# LV_power.net
KiCad netlist of a schematic drawn in Altium Designer
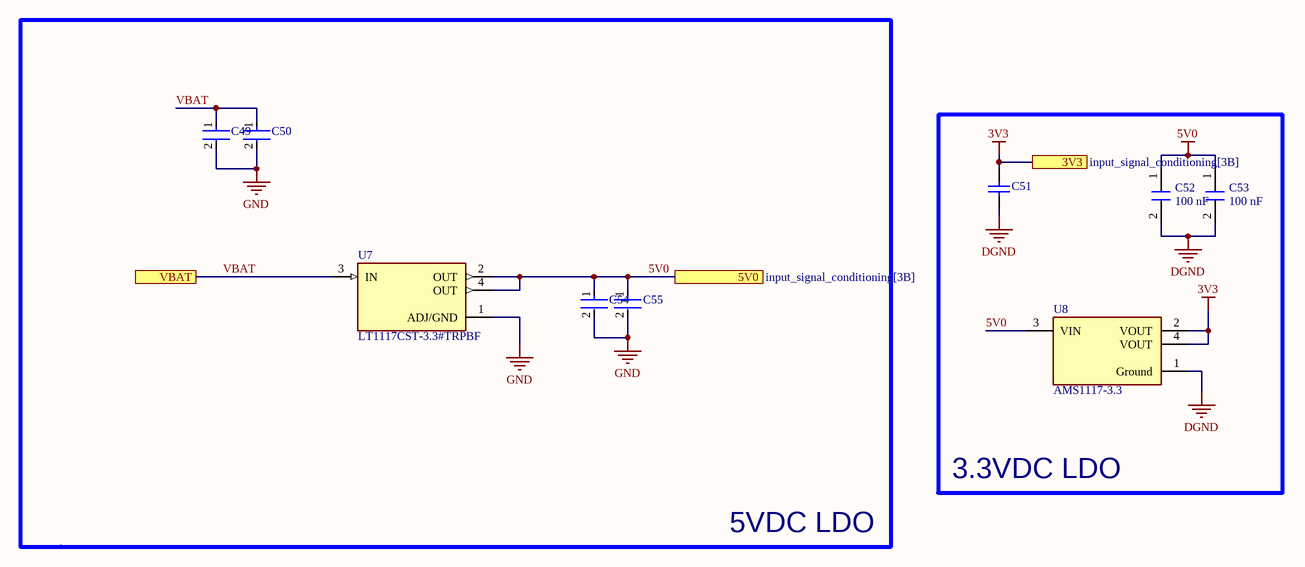
[diagram p0: LV_power.SchDoc]

(export (version "E")
  (design (tool "Eeschema 10.0.6"))
  (components
    (comp (ref "C49")
      (value "CC0805MKX5R8BB226")
      (footprint "FP-CC0805-0_2-1_45-IPC_C")
      (description "CAP CER 22UF 25V X5R 0805")
      (fields (field (name "TOLERANCE") "20%"))
      (libsource (lib "Altium Content Vault") (part "11868f565c42a9108669ba33697ecf6"))
    )
    (comp (ref "C50")
      (value "CC0805MKX5R8BB226")
      (footprint "FP-CC0805-0_2-1_45-IPC_C")
      (description "CAP CER 22UF 25V X5R 0805")
      (fields (field (name "TOLERANCE") "20%"))
      (libsource (lib "Altium Content Vault") (part "11868f565c42a9108669ba33697ecf6"))
    )
    (comp (ref "C51")
      (value "0805ZG106ZAT2A")
      (footprint "CAPC2013X152X50NL20T25")
      (fields (field (name "MANUFACTURER") "AVX Interconnect / Elco"))
      (libsource (lib "Altium Content Vault") (part "CAP"))
    )
    (comp (ref "C52")
      (value "100 nF")
      (footprint "0603_FP")
      (fields (field (name "Comment") "Capacitor_0603"))
      (libsource (lib "RC_sch") (part "Capacitor_0603"))
    )
    (comp (ref "C53")
      (value "100 nF")
      (footprint "0603_FP")
      (fields (field (name "Comment") "Capacitor_0603"))
      (libsource (lib "RC_sch") (part "Capacitor_0603"))
    )
    (comp (ref "C54")
      (value "GRM21BR61A476ME15K")
      (footprint "FP-GRM21B-0_2-e0_2_0_7-IPC_B")
      (description "Chip Multilayer Ceramic Capacitors for General Purpose, 0805, 47uF, X5R, 15%, 20%, 10V")
      (fields (field (name "TOLERANCE") "20%"))
      (libsource (lib "Altium Content Vault") (part "b4654b650e69147ec39a6b967a45e02"))
    )
    (comp (ref "C55")
      (value "GRM21BR61A476ME15K")
      (footprint "FP-GRM21B-0_2-e0_2_0_7-IPC_B")
      (description "Chip Multilayer Ceramic Capacitors for General Purpose, 0805, 47uF, X5R, 15%, 20%, 10V")
      (fields (field (name "TOLERANCE") "20%"))
      (libsource (lib "Altium Content Vault") (part "b4654b650e69147ec39a6b967a45e02"))
    )
    (comp (ref "U7")
      (value "LT1117CST-3.3#TRPBF")
      (footprint "REG_LT1117CST-3.3#TRPBF")
      (description "LT1117 - 800mA Low Dropout Positive Regulators Adjustable and Fixed 2.85V, 3.3V, 5V")
      (fields (field (name "MF") "{'manufacturer': u'Analog Devices Inc.'}"))
      (libsource (lib "LT1117CST-3.3_TRPBF") (part "LT1117CST-3.3#TRPBF"))
    )
    (comp (ref "U8")
      (value "AMS1117-3.3")
      (footprint "FP-AMS1117-IPC_C")
      (description "LDO Voltage Regulators 1A, 3.3V")
      (fields
        (field (name "OCTOPART") "https://octopart.com/ams1117-3.3-advanced+monolithic+systems-25899300")
        (field (name "MANUFACTURER") "Advanced Monolithic Systems")
      )
      (libsource (lib "Altium Content Vault") (part "8bdbb5f8e77002000e30dd2845d0354"))
    )
  )
  (nets
    (net (code "1") (name "/VBAT") (class "Default")
      (node (ref "C49") (pin "1") (pinfunction "1_1") (pintype "passive"))
      (node (ref "C50") (pin "1") (pinfunction "1_1") (pintype "passive"))
      (node (ref "U7") (pin "3") (pinfunction "IN_3") (pintype "input"))
    )
    (net (code "2") (name "3V3") (class "Default")
      (node (ref "C51") (pin "2") (pinfunction "2_2") (pintype "passive"))
      (node (ref "U8") (pin "2") (pinfunction "VOUT_2") (pintype "passive"))
      (node (ref "U8") (pin "4") (pinfunction "VOUT_4") (pintype "passive"))
    )
    (net (code "3") (name "5V0") (class "Default")
      (node (ref "C52") (pin "1") (pinfunction "1_1") (pintype "passive"))
      (node (ref "C53") (pin "1") (pinfunction "1_1") (pintype "passive"))
      (node (ref "C54") (pin "1") (pinfunction "1_1") (pintype "passive"))
      (node (ref "C55") (pin "1") (pinfunction "1_1") (pintype "passive"))
      (node (ref "U7") (pin "2") (pinfunction "OUT_2") (pintype "output"))
      (node (ref "U7") (pin "4") (pinfunction "OUT_4") (pintype "output"))
      (node (ref "U8") (pin "3") (pinfunction "VIN_3") (pintype "power_in"))
    )
    (net (code "4") (name "DGND") (class "Default")
      (node (ref "C51") (pin "1") (pinfunction "1_1") (pintype "passive"))
      (node (ref "C52") (pin "2") (pinfunction "2_2") (pintype "passive"))
      (node (ref "C53") (pin "2") (pinfunction "2_2") (pintype "passive"))
      (node (ref "U8") (pin "1") (pinfunction "Ground_1") (pintype "power_in"))
    )
    (net (code "5") (name "GND") (class "Default")
      (node (ref "C49") (pin "2") (pinfunction "2_2") (pintype "passive"))
      (node (ref "C50") (pin "2") (pinfunction "2_2") (pintype "passive"))
      (node (ref "C54") (pin "2") (pinfunction "2_2") (pintype "passive"))
      (node (ref "C55") (pin "2") (pinfunction "2_2") (pintype "passive"))
      (node (ref "U7") (pin "1") (pinfunction "ADJ/GND_1") (pintype "power_in"))
    )
  )
)
